# FPGA_System_Monitor.net
KiCad netlist of a schematic drawn in Altium Designer
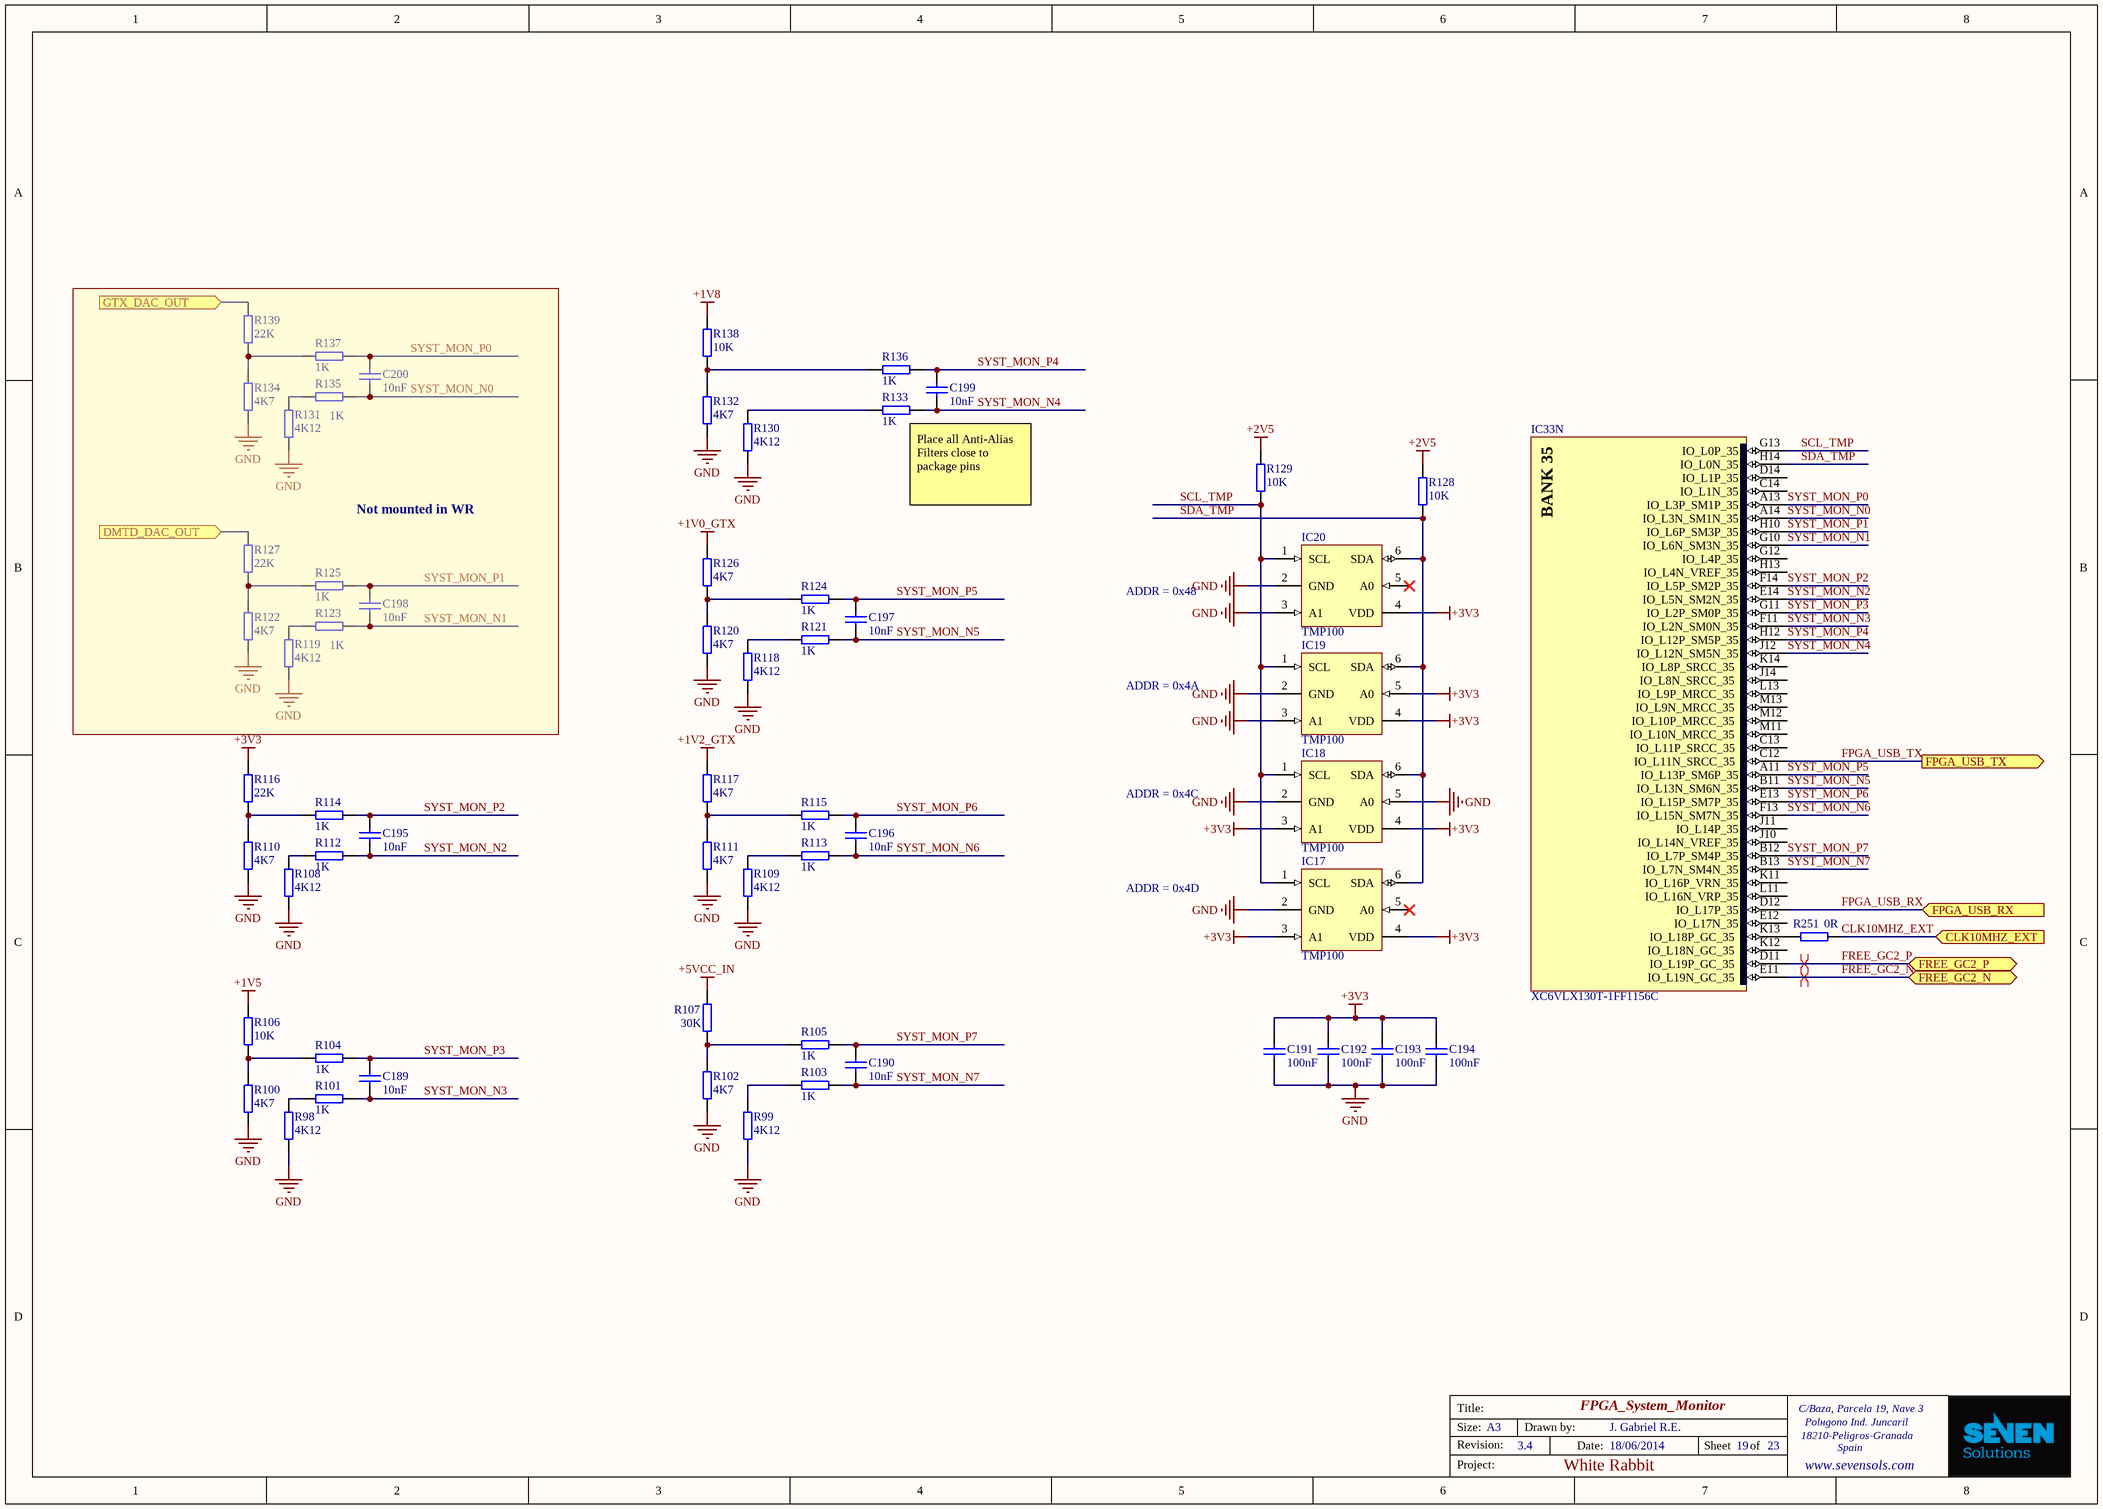
[diagram p0: FPGA_System_Monitor.SchDoc]

(export (version "E")
  (design (tool "Eeschema 10.0.6"))
  (components
    (comp (ref "C189")
      (value "10nF")
      (footprint "CC1005-0402")
      (description "Capacitor")
      (fields
        (field (name "TOLERANCE") "±10%")
        (field (name "VOLTAGE") "25V")
        (field (name "PUBLISHER") "Altium Limited")
      )
      (libsource (lib "wr_switch") (part "Cap"))
    )
    (comp (ref "C190")
      (value "10nF")
      (footprint "CC1005-0402")
      (description "Capacitor")
      (fields
        (field (name "TOLERANCE") "±10%")
        (field (name "VOLTAGE") "25V")
        (field (name "PUBLISHER") "Altium Limited")
      )
      (libsource (lib "wr_switch") (part "Cap"))
    )
    (comp (ref "C191")
      (value "100nF")
      (footprint "CC1005-0402")
      (description "Capacitor")
      (fields
        (field (name "TOLERANCE") "±10%")
        (field (name "VOLTAGE") "16V")
        (field (name "PUBLISHER") "Altium Limited")
      )
      (libsource (lib "wr_switch") (part "Cap"))
    )
    (comp (ref "C192")
      (value "100nF")
      (footprint "CC1005-0402")
      (description "Capacitor")
      (fields
        (field (name "TOLERANCE") "±10%")
        (field (name "VOLTAGE") "16V")
        (field (name "PUBLISHER") "Altium Limited")
      )
      (libsource (lib "wr_switch") (part "Cap"))
    )
    (comp (ref "C193")
      (value "100nF")
      (footprint "CC1005-0402")
      (description "Capacitor")
      (fields
        (field (name "TOLERANCE") "±10%")
        (field (name "VOLTAGE") "16V")
        (field (name "PUBLISHER") "Altium Limited")
      )
      (libsource (lib "wr_switch") (part "Cap"))
    )
    (comp (ref "C194")
      (value "100nF")
      (footprint "CC1005-0402")
      (description "Capacitor")
      (fields
        (field (name "TOLERANCE") "±10%")
        (field (name "VOLTAGE") "16V")
        (field (name "PUBLISHER") "Altium Limited")
      )
      (libsource (lib "wr_switch") (part "Cap"))
    )
    (comp (ref "C195")
      (value "10nF")
      (footprint "CC1005-0402")
      (description "Capacitor")
      (fields
        (field (name "TOLERANCE") "±10%")
        (field (name "VOLTAGE") "25V")
        (field (name "PUBLISHER") "Altium Limited")
      )
      (libsource (lib "wr_switch") (part "Cap"))
    )
    (comp (ref "C196")
      (value "10nF")
      (footprint "CC1005-0402")
      (description "Capacitor")
      (fields
        (field (name "TOLERANCE") "±10%")
        (field (name "VOLTAGE") "25V")
        (field (name "PUBLISHER") "Altium Limited")
      )
      (libsource (lib "wr_switch") (part "Cap"))
    )
    (comp (ref "C197")
      (value "10nF")
      (footprint "CC1005-0402")
      (description "Capacitor")
      (fields
        (field (name "TOLERANCE") "±10%")
        (field (name "VOLTAGE") "25V")
        (field (name "PUBLISHER") "Altium Limited")
      )
      (libsource (lib "wr_switch") (part "Cap"))
    )
    (comp (ref "C198")
      (value "10nF")
      (footprint "CC1005-0402")
      (description "Capacitor")
      (fields
        (field (name "TOLERANCE") "±10%")
        (field (name "VOLTAGE") "25V")
        (field (name "PUBLISHER") "Altium Limited")
      )
      (libsource (lib "wr_switch") (part "Cap"))
    )
    (comp (ref "C199")
      (value "10nF")
      (footprint "CC1005-0402")
      (description "Capacitor")
      (fields
        (field (name "TOLERANCE") "±10%")
        (field (name "VOLTAGE") "25V")
        (field (name "PUBLISHER") "Altium Limited")
      )
      (libsource (lib "wr_switch") (part "Cap"))
    )
    (comp (ref "C200")
      (value "10nF")
      (footprint "CC1005-0402")
      (description "Capacitor")
      (fields
        (field (name "TOLERANCE") "±10%")
        (field (name "VOLTAGE") "25V")
        (field (name "PUBLISHER") "Altium Limited")
      )
      (libsource (lib "wr_switch") (part "Cap"))
    )
    (comp (ref "IC17")
      (value "TMP100")
      (footprint "SOT23A-6L")
      (description "I2C temp. sensor")
      (libsource (lib "wr_switch") (part "TMP100"))
    )
    (comp (ref "IC18")
      (value "TMP100")
      (footprint "SOT23A-6L")
      (description "I2C temp. sensor")
      (libsource (lib "wr_switch") (part "TMP100"))
    )
    (comp (ref "IC19")
      (value "TMP100")
      (footprint "SOT23A-6L")
      (description "I2C temp. sensor")
      (libsource (lib "wr_switch") (part "TMP100"))
    )
    (comp (ref "IC20")
      (value "TMP100")
      (footprint "SOT23A-6L")
      (description "I2C temp. sensor")
      (libsource (lib "wr_switch") (part "TMP100"))
    )
    (comp (ref "IC33")
      (value "XC6VLX130T-1FF1156C")
      (footprint "FF1156")
      (fields (field (name "PUBLISHER") "Altium Limited"))
      (libsource (lib "Xilinx Virtex-6") (part "XC6VLX130T-1FF1156C"))
    )
    (comp (ref "R98")
      (value "4K12")
      (footprint "0402")
      (description "SMD Resistor")
      (fields (field (name "TOLERANCE") "±1%"))
      (libsource (lib "wr_switch") (part "RES_SMD"))
    )
    (comp (ref "R99")
      (value "4K12")
      (footprint "0402")
      (description "SMD Resistor")
      (fields (field (name "TOLERANCE") "±1%"))
      (libsource (lib "wr_switch") (part "RES_SMD"))
    )
    (comp (ref "R100")
      (value "4K7")
      (footprint "0402")
      (description "SMD Resistor")
      (fields (field (name "TOLERANCE") "±1%"))
      (libsource (lib "wr_switch") (part "RES_SMD"))
    )
    (comp (ref "R101")
      (value "1K")
      (footprint "0402")
      (description "SMD Resistor")
      (fields (field (name "TOLERANCE") "±1%"))
      (libsource (lib "wr_switch") (part "RES_SMD"))
    )
    (comp (ref "R102")
      (value "4K7")
      (footprint "0402")
      (description "SMD Resistor")
      (fields (field (name "TOLERANCE") "±1%"))
      (libsource (lib "wr_switch") (part "RES_SMD"))
    )
    (comp (ref "R103")
      (value "1K")
      (footprint "0402")
      (description "SMD Resistor")
      (fields (field (name "TOLERANCE") "±1%"))
      (libsource (lib "wr_switch") (part "RES_SMD"))
    )
    (comp (ref "R104")
      (value "1K")
      (footprint "0402")
      (description "SMD Resistor")
      (fields (field (name "TOLERANCE") "±1%"))
      (libsource (lib "wr_switch") (part "RES_SMD"))
    )
    (comp (ref "R105")
      (value "1K")
      (footprint "0402")
      (description "SMD Resistor")
      (fields (field (name "TOLERANCE") "±1%"))
      (libsource (lib "wr_switch") (part "RES_SMD"))
    )
    (comp (ref "R106")
      (value "10K")
      (footprint "0402")
      (description "SMD Resistor")
      (fields (field (name "TOLERANCE") "±1%") (field (name "Comment") "10k"))
      (libsource (lib "wr_switch") (part "RES_SMD"))
    )
    (comp (ref "R107")
      (value "30K")
      (footprint "0402")
      (description "SMD Resistor")
      (fields (field (name "TOLERANCE") "±1%"))
      (libsource (lib "wr_switch") (part "RES_SMD"))
    )
    (comp (ref "R108")
      (value "4K12")
      (footprint "0402")
      (description "SMD Resistor")
      (fields (field (name "TOLERANCE") "±1%"))
      (libsource (lib "wr_switch") (part "RES_SMD"))
    )
    (comp (ref "R109")
      (value "4K12")
      (footprint "0402")
      (description "SMD Resistor")
      (fields (field (name "TOLERANCE") "±1%"))
      (libsource (lib "wr_switch") (part "RES_SMD"))
    )
    (comp (ref "R110")
      (value "4K7")
      (footprint "0402")
      (description "SMD Resistor")
      (fields (field (name "TOLERANCE") "±1%"))
      (libsource (lib "wr_switch") (part "RES_SMD"))
    )
    (comp (ref "R111")
      (value "4K7")
      (footprint "0402")
      (description "SMD Resistor")
      (fields (field (name "TOLERANCE") "±1%"))
      (libsource (lib "wr_switch") (part "RES_SMD"))
    )
    (comp (ref "R112")
      (value "1K")
      (footprint "0402")
      (description "SMD Resistor")
      (fields (field (name "TOLERANCE") "±1%"))
      (libsource (lib "wr_switch") (part "RES_SMD"))
    )
    (comp (ref "R113")
      (value "1K")
      (footprint "0402")
      (description "SMD Resistor")
      (fields (field (name "TOLERANCE") "±1%"))
      (libsource (lib "wr_switch") (part "RES_SMD"))
    )
    (comp (ref "R114")
      (value "1K")
      (footprint "0402")
      (description "SMD Resistor")
      (fields (field (name "TOLERANCE") "±1%"))
      (libsource (lib "wr_switch") (part "RES_SMD"))
    )
    (comp (ref "R115")
      (value "1K")
      (footprint "0402")
      (description "SMD Resistor")
      (fields (field (name "TOLERANCE") "±1%"))
      (libsource (lib "wr_switch") (part "RES_SMD"))
    )
    (comp (ref "R116")
      (value "22K")
      (footprint "0402")
      (description "SMD Resistor")
      (fields (field (name "TOLERANCE") "±1%"))
      (libsource (lib "wr_switch") (part "RES_SMD"))
    )
    (comp (ref "R117")
      (value "4K7")
      (footprint "0402")
      (description "SMD Resistor")
      (fields (field (name "TOLERANCE") "±1%"))
      (libsource (lib "wr_switch") (part "RES_SMD"))
    )
    (comp (ref "R118")
      (value "4K12")
      (footprint "0402")
      (description "SMD Resistor")
      (fields (field (name "TOLERANCE") "±1%"))
      (libsource (lib "wr_switch") (part "RES_SMD"))
    )
    (comp (ref "R119")
      (value "4K12")
      (footprint "0402")
      (description "SMD Resistor")
      (fields (field (name "TOLERANCE") "±1%"))
      (libsource (lib "wr_switch") (part "RES_SMD"))
    )
    (comp (ref "R120")
      (value "4K7")
      (footprint "0402")
      (description "SMD Resistor")
      (fields (field (name "TOLERANCE") "±1%"))
      (libsource (lib "wr_switch") (part "RES_SMD"))
    )
    (comp (ref "R121")
      (value "1K")
      (footprint "0402")
      (description "SMD Resistor")
      (fields (field (name "TOLERANCE") "±1%"))
      (libsource (lib "wr_switch") (part "RES_SMD"))
    )
    (comp (ref "R122")
      (value "4K7")
      (footprint "0402")
      (description "SMD Resistor")
      (fields (field (name "TOLERANCE") "±1%"))
      (libsource (lib "wr_switch") (part "RES_SMD"))
    )
    (comp (ref "R123")
      (value "1K")
      (footprint "0402")
      (description "SMD Resistor")
      (fields (field (name "TOLERANCE") "±1%"))
      (libsource (lib "wr_switch") (part "RES_SMD"))
    )
    (comp (ref "R124")
      (value "1K")
      (footprint "0402")
      (description "SMD Resistor")
      (fields (field (name "TOLERANCE") "±1%"))
      (libsource (lib "wr_switch") (part "RES_SMD"))
    )
    (comp (ref "R125")
      (value "1K")
      (footprint "0402")
      (description "SMD Resistor")
      (fields (field (name "TOLERANCE") "±1%"))
      (libsource (lib "wr_switch") (part "RES_SMD"))
    )
    (comp (ref "R126")
      (value "4K7")
      (footprint "0402")
      (description "SMD Resistor")
      (fields (field (name "TOLERANCE") "±1%"))
      (libsource (lib "wr_switch") (part "RES_SMD"))
    )
    (comp (ref "R127")
      (value "22K")
      (footprint "0402")
      (description "SMD Resistor")
      (fields (field (name "TOLERANCE") "±1%"))
      (libsource (lib "wr_switch") (part "RES_SMD"))
    )
    (comp (ref "R128")
      (value "10K")
      (footprint "0402")
      (description "SMD Resistor")
      (fields (field (name "TOLERANCE") "±1%") (field (name "Comment") "10k"))
      (libsource (lib "wr_switch") (part "RES_SMD"))
    )
    (comp (ref "R129")
      (value "10K")
      (footprint "0402")
      (description "SMD Resistor")
      (fields (field (name "TOLERANCE") "±1%") (field (name "Comment") "10k"))
      (libsource (lib "wr_switch") (part "RES_SMD"))
    )
    (comp (ref "R130")
      (value "4K12")
      (footprint "0402")
      (description "SMD Resistor")
      (fields (field (name "TOLERANCE") "±1%"))
      (libsource (lib "wr_switch") (part "RES_SMD"))
    )
    (comp (ref "R131")
      (value "4K12")
      (footprint "0402")
      (description "SMD Resistor")
      (fields (field (name "TOLERANCE") "±1%"))
      (libsource (lib "wr_switch") (part "RES_SMD"))
    )
    (comp (ref "R132")
      (value "4K7")
      (footprint "0402")
      (description "SMD Resistor")
      (fields (field (name "TOLERANCE") "±1%"))
      (libsource (lib "wr_switch") (part "RES_SMD"))
    )
    (comp (ref "R133")
      (value "1K")
      (footprint "0402")
      (description "SMD Resistor")
      (fields (field (name "TOLERANCE") "±1%"))
      (libsource (lib "wr_switch") (part "RES_SMD"))
    )
    (comp (ref "R134")
      (value "4K7")
      (footprint "0402")
      (description "SMD Resistor")
      (fields (field (name "TOLERANCE") "±1%"))
      (libsource (lib "wr_switch") (part "RES_SMD"))
    )
    (comp (ref "R135")
      (value "1K")
      (footprint "0402")
      (description "SMD Resistor")
      (fields (field (name "TOLERANCE") "±1%"))
      (libsource (lib "wr_switch") (part "RES_SMD"))
    )
    (comp (ref "R136")
      (value "1K")
      (footprint "0402")
      (description "SMD Resistor")
      (fields (field (name "TOLERANCE") "±1%"))
      (libsource (lib "wr_switch") (part "RES_SMD"))
    )
    (comp (ref "R137")
      (value "1K")
      (footprint "0402")
      (description "SMD Resistor")
      (fields (field (name "TOLERANCE") "±1%"))
      (libsource (lib "wr_switch") (part "RES_SMD"))
    )
    (comp (ref "R138")
      (value "10K")
      (footprint "0402")
      (description "SMD Resistor")
      (fields (field (name "TOLERANCE") "±1%") (field (name "Comment") "10k"))
      (libsource (lib "wr_switch") (part "RES_SMD"))
    )
    (comp (ref "R139")
      (value "22K")
      (footprint "0402")
      (description "SMD Resistor")
      (fields (field (name "TOLERANCE") "±1%"))
      (libsource (lib "wr_switch") (part "RES_SMD"))
    )
    (comp (ref "R251")
      (value "0R")
      (footprint "0402")
      (description "SMD Resistor")
      (fields (field (name "TOLERANCE") "Jumper"))
      (libsource (lib "wr_switch") (part "RES_SMD"))
    )
  )
  (nets
    (net (code "1") (name "+1V0_GTX") (class "Default")
      (node (ref "R126") (pin "2") (pinfunction "2_2") (pintype "passive"))
    )
    (net (code "2") (name "+1V2_GTX") (class "Default")
      (node (ref "R117") (pin "2") (pinfunction "2_2") (pintype "passive"))
    )
    (net (code "3") (name "+1V5") (class "Default")
      (node (ref "R106") (pin "2") (pinfunction "2_2") (pintype "passive"))
    )
    (net (code "4") (name "+1V8") (class "Default")
      (node (ref "R138") (pin "2") (pinfunction "2_2") (pintype "passive"))
    )
    (net (code "5") (name "+2V5") (class "Default")
      (node (ref "R128") (pin "2") (pinfunction "2_2") (pintype "passive"))
      (node (ref "R129") (pin "2") (pinfunction "2_2") (pintype "passive"))
    )
    (net (code "6") (name "+3V3") (class "Default")
      (node (ref "C191") (pin "1") (pinfunction "1_1") (pintype "passive"))
      (node (ref "C192") (pin "1") (pinfunction "1_1") (pintype "passive"))
      (node (ref "C193") (pin "1") (pinfunction "1_1") (pintype "passive"))
      (node (ref "C194") (pin "1") (pinfunction "1_1") (pintype "passive"))
      (node (ref "IC17") (pin "3") (pinfunction "A1_3") (pintype "input"))
      (node (ref "IC17") (pin "4") (pinfunction "VDD_4") (pintype "power_in"))
      (node (ref "IC18") (pin "3") (pinfunction "A1_3") (pintype "input"))
      (node (ref "IC18") (pin "4") (pinfunction "VDD_4") (pintype "power_in"))
      (node (ref "IC19") (pin "4") (pinfunction "VDD_4") (pintype "power_in"))
      (node (ref "IC19") (pin "5") (pinfunction "A0_5") (pintype "input"))
      (node (ref "IC20") (pin "4") (pinfunction "VDD_4") (pintype "power_in"))
      (node (ref "R116") (pin "2") (pinfunction "2_2") (pintype "passive"))
    )
    (net (code "7") (name "+5VCC_IN") (class "Default")
      (node (ref "R107") (pin "2") (pinfunction "2_2") (pintype "passive"))
    )
    (net (code "8") (name "/CLK10MHZ_EXT") (class "Default")
      (node (ref "R251") (pin "1") (pinfunction "1_1") (pintype "passive"))
    )
    (net (code "9") (name "/DMTD_DAC_OUT") (class "Default")
      (node (ref "R127") (pin "2") (pinfunction "2_2") (pintype "passive"))
    )
    (net (code "10") (name "/FPGA_USB_RX") (class "Default")
      (node (ref "IC33") (pin "D12") (pinfunction "IO_L17P_35_D12") (pintype "bidirectional"))
    )
    (net (code "11") (name "/FPGA_USB_TX") (class "Default")
      (node (ref "IC33") (pin "C12") (pinfunction "IO_L11N_SRCC_35_C12") (pintype "bidirectional"))
    )
    (net (code "12") (name "/FREE_GC2_N") (class "Default")
      (node (ref "IC33") (pin "E11") (pinfunction "IO_L19N_GC_35_E11") (pintype "bidirectional"))
    )
    (net (code "13") (name "/FREE_GC2_P") (class "Default")
      (node (ref "IC33") (pin "D11") (pinfunction "IO_L19P_GC_35_D11") (pintype "bidirectional"))
    )
    (net (code "14") (name "/GTX_DAC_OUT") (class "Default")
      (node (ref "R139") (pin "2") (pinfunction "2_2") (pintype "passive"))
    )
    (net (code "15") (name "/SCL_TMP") (class "Default")
      (node (ref "IC17") (pin "1") (pinfunction "SCL_1") (pintype "input"))
      (node (ref "IC18") (pin "1") (pinfunction "SCL_1") (pintype "input"))
      (node (ref "IC19") (pin "1") (pinfunction "SCL_1") (pintype "input"))
      (node (ref "IC20") (pin "1") (pinfunction "SCL_1") (pintype "input"))
      (node (ref "IC33") (pin "G13") (pinfunction "IO_L0P_35_G13") (pintype "bidirectional"))
      (node (ref "R129") (pin "1") (pinfunction "1_1") (pintype "passive"))
    )
    (net (code "16") (name "/SDA_TMP") (class "Default")
      (node (ref "IC17") (pin "6") (pinfunction "SDA_6") (pintype "bidirectional"))
      (node (ref "IC18") (pin "6") (pinfunction "SDA_6") (pintype "bidirectional"))
      (node (ref "IC19") (pin "6") (pinfunction "SDA_6") (pintype "bidirectional"))
      (node (ref "IC20") (pin "6") (pinfunction "SDA_6") (pintype "bidirectional"))
      (node (ref "IC33") (pin "H14") (pinfunction "IO_L0N_35_H14") (pintype "bidirectional"))
      (node (ref "R128") (pin "1") (pinfunction "1_1") (pintype "passive"))
    )
    (net (code "17") (name "/SYST_MON_N0") (class "Default")
      (node (ref "C200") (pin "1") (pinfunction "1_1") (pintype "passive"))
      (node (ref "IC33") (pin "A14") (pinfunction "IO_L3N_SM1N_35_A14") (pintype "bidirectional"))
      (node (ref "R135") (pin "1") (pinfunction "1_1") (pintype "passive"))
    )
    (net (code "18") (name "/SYST_MON_N1") (class "Default")
      (node (ref "C198") (pin "1") (pinfunction "1_1") (pintype "passive"))
      (node (ref "IC33") (pin "G10") (pinfunction "IO_L6N_SM3N_35_G10") (pintype "bidirectional"))
      (node (ref "R123") (pin "1") (pinfunction "1_1") (pintype "passive"))
    )
    (net (code "19") (name "/SYST_MON_N2") (class "Default")
      (node (ref "C195") (pin "1") (pinfunction "1_1") (pintype "passive"))
      (node (ref "IC33") (pin "E14") (pinfunction "IO_L5N_SM2N_35_E14") (pintype "bidirectional"))
      (node (ref "R112") (pin "1") (pinfunction "1_1") (pintype "passive"))
    )
    (net (code "20") (name "/SYST_MON_N3") (class "Default")
      (node (ref "C189") (pin "1") (pinfunction "1_1") (pintype "passive"))
      (node (ref "IC33") (pin "F11") (pinfunction "IO_L2N_SM0N_35_F11") (pintype "bidirectional"))
      (node (ref "R101") (pin "1") (pinfunction "1_1") (pintype "passive"))
    )
    (net (code "21") (name "/SYST_MON_N4") (class "Default")
      (node (ref "C199") (pin "1") (pinfunction "1_1") (pintype "passive"))
      (node (ref "IC33") (pin "J12") (pinfunction "IO_L12N_SM5N_35_J12") (pintype "bidirectional"))
      (node (ref "R133") (pin "1") (pinfunction "1_1") (pintype "passive"))
    )
    (net (code "22") (name "/SYST_MON_N5") (class "Default")
      (node (ref "C197") (pin "1") (pinfunction "1_1") (pintype "passive"))
      (node (ref "IC33") (pin "B11") (pinfunction "IO_L13N_SM6N_35_B11") (pintype "bidirectional"))
      (node (ref "R121") (pin "1") (pinfunction "1_1") (pintype "passive"))
    )
    (net (code "23") (name "/SYST_MON_N6") (class "Default")
      (node (ref "C196") (pin "1") (pinfunction "1_1") (pintype "passive"))
      (node (ref "IC33") (pin "F13") (pinfunction "IO_L15N_SM7N_35_F13") (pintype "bidirectional"))
      (node (ref "R113") (pin "1") (pinfunction "1_1") (pintype "passive"))
    )
    (net (code "24") (name "/SYST_MON_N7") (class "Default")
      (node (ref "C190") (pin "1") (pinfunction "1_1") (pintype "passive"))
      (node (ref "IC33") (pin "B13") (pinfunction "IO_L7N_SM4N_35_B13") (pintype "bidirectional"))
      (node (ref "R103") (pin "1") (pinfunction "1_1") (pintype "passive"))
    )
    (net (code "25") (name "/SYST_MON_P0") (class "Default")
      (node (ref "C200") (pin "2") (pinfunction "2_2") (pintype "passive"))
      (node (ref "IC33") (pin "A13") (pinfunction "IO_L3P_SM1P_35_A13") (pintype "bidirectional"))
      (node (ref "R137") (pin "1") (pinfunction "1_1") (pintype "passive"))
    )
    (net (code "26") (name "/SYST_MON_P1") (class "Default")
      (node (ref "C198") (pin "2") (pinfunction "2_2") (pintype "passive"))
      (node (ref "IC33") (pin "H10") (pinfunction "IO_L6P_SM3P_35_H10") (pintype "bidirectional"))
      (node (ref "R125") (pin "1") (pinfunction "1_1") (pintype "passive"))
    )
    (net (code "27") (name "/SYST_MON_P2") (class "Default")
      (node (ref "C195") (pin "2") (pinfunction "2_2") (pintype "passive"))
      (node (ref "IC33") (pin "F14") (pinfunction "IO_L5P_SM2P_35_F14") (pintype "bidirectional"))
      (node (ref "R114") (pin "1") (pinfunction "1_1") (pintype "passive"))
    )
    (net (code "28") (name "/SYST_MON_P3") (class "Default")
      (node (ref "C189") (pin "2") (pinfunction "2_2") (pintype "passive"))
      (node (ref "IC33") (pin "G11") (pinfunction "IO_L2P_SM0P_35_G11") (pintype "bidirectional"))
      (node (ref "R104") (pin "1") (pinfunction "1_1") (pintype "passive"))
    )
    (net (code "29") (name "/SYST_MON_P4") (class "Default")
      (node (ref "C199") (pin "2") (pinfunction "2_2") (pintype "passive"))
      (node (ref "IC33") (pin "H12") (pinfunction "IO_L12P_SM5P_35_H12") (pintype "bidirectional"))
      (node (ref "R136") (pin "1") (pinfunction "1_1") (pintype "passive"))
    )
    (net (code "30") (name "/SYST_MON_P5") (class "Default")
      (node (ref "C197") (pin "2") (pinfunction "2_2") (pintype "passive"))
      (node (ref "IC33") (pin "A11") (pinfunction "IO_L13P_SM6P_35_A11") (pintype "bidirectional"))
      (node (ref "R124") (pin "1") (pinfunction "1_1") (pintype "passive"))
    )
    (net (code "31") (name "/SYST_MON_P6") (class "Default")
      (node (ref "C196") (pin "2") (pinfunction "2_2") (pintype "passive"))
      (node (ref "IC33") (pin "E13") (pinfunction "IO_L15P_SM7P_35_E13") (pintype "bidirectional"))
      (node (ref "R115") (pin "1") (pinfunction "1_1") (pintype "passive"))
    )
    (net (code "32") (name "/SYST_MON_P7") (class "Default")
      (node (ref "C190") (pin "2") (pinfunction "2_2") (pintype "passive"))
      (node (ref "IC33") (pin "B12") (pinfunction "IO_L7P_SM4P_35_B12") (pintype "bidirectional"))
      (node (ref "R105") (pin "1") (pinfunction "1_1") (pintype "passive"))
    )
    (net (code "33") (name "GND") (class "Default")
      (node (ref "C191") (pin "2") (pinfunction "2_2") (pintype "passive"))
      (node (ref "C192") (pin "2") (pinfunction "2_2") (pintype "passive"))
      (node (ref "C193") (pin "2") (pinfunction "2_2") (pintype "passive"))
      (node (ref "C194") (pin "2") (pinfunction "2_2") (pintype "passive"))
      (node (ref "IC17") (pin "2") (pinfunction "GND_2") (pintype "power_in"))
      (node (ref "IC18") (pin "2") (pinfunction "GND_2") (pintype "power_in"))
      (node (ref "IC18") (pin "5") (pinfunction "A0_5") (pintype "input"))
      (node (ref "IC19") (pin "2") (pinfunction "GND_2") (pintype "power_in"))
      (node (ref "IC19") (pin "3") (pinfunction "A1_3") (pintype "input"))
      (node (ref "IC20") (pin "2") (pinfunction "GND_2") (pintype "power_in"))
      (node (ref "IC20") (pin "3") (pinfunction "A1_3") (pintype "input"))
      (node (ref "R100") (pin "1") (pinfunction "1_1") (pintype "passive"))
      (node (ref "R102") (pin "1") (pinfunction "1_1") (pintype "passive"))
      (node (ref "R108") (pin "1") (pinfunction "1_1") (pintype "passive"))
      (node (ref "R109") (pin "1") (pinfunction "1_1") (pintype "passive"))
      (node (ref "R110") (pin "1") (pinfunction "1_1") (pintype "passive"))
      (node (ref "R111") (pin "1") (pinfunction "1_1") (pintype "passive"))
      (node (ref "R118") (pin "1") (pinfunction "1_1") (pintype "passive"))
      (node (ref "R119") (pin "1") (pinfunction "1_1") (pintype "passive"))
      (node (ref "R120") (pin "1") (pinfunction "1_1") (pintype "passive"))
      (node (ref "R122") (pin "1") (pinfunction "1_1") (pintype "passive"))
      (node (ref "R130") (pin "1") (pinfunction "1_1") (pintype "passive"))
      (node (ref "R131") (pin "1") (pinfunction "1_1") (pintype "passive"))
      (node (ref "R132") (pin "1") (pinfunction "1_1") (pintype "passive"))
      (node (ref "R134") (pin "1") (pinfunction "1_1") (pintype "passive"))
      (node (ref "R98") (pin "1") (pinfunction "1_1") (pintype "passive"))
      (node (ref "R99") (pin "1") (pinfunction "1_1") (pintype "passive"))
    )
    (net (code "34") (name "Net-(IC33N-IO_L18P_GC_35)") (class "Default")
      (node (ref "IC33") (pin "K13") (pinfunction "IO_L18P_GC_35_K13") (pintype "bidirectional"))
      (node (ref "R251") (pin "2") (pinfunction "2_2") (pintype "passive"))
    )
    (net (code "35") (name "Net-(R100-Pad2)") (class "Default")
      (node (ref "R100") (pin "2") (pinfunction "2_2") (pintype "passive"))
      (node (ref "R104") (pin "2") (pinfunction "2_2") (pintype "passive"))
      (node (ref "R106") (pin "1") (pinfunction "1_1") (pintype "passive"))
    )
    (net (code "36") (name "Net-(R101-Pad2)") (class "Default")
      (node (ref "R101") (pin "2") (pinfunction "2_2") (pintype "passive"))
      (node (ref "R98") (pin "2") (pinfunction "2_2") (pintype "passive"))
    )
    (net (code "37") (name "Net-(R102-Pad2)") (class "Default")
      (node (ref "R102") (pin "2") (pinfunction "2_2") (pintype "passive"))
      (node (ref "R105") (pin "2") (pinfunction "2_2") (pintype "passive"))
      (node (ref "R107") (pin "1") (pinfunction "1_1") (pintype "passive"))
    )
    (net (code "38") (name "Net-(R103-Pad2)") (class "Default")
      (node (ref "R103") (pin "2") (pinfunction "2_2") (pintype "passive"))
      (node (ref "R99") (pin "2") (pinfunction "2_2") (pintype "passive"))
    )
    (net (code "39") (name "Net-(R108-Pad2)") (class "Default")
      (node (ref "R108") (pin "2") (pinfunction "2_2") (pintype "passive"))
      (node (ref "R112") (pin "2") (pinfunction "2_2") (pintype "passive"))
    )
    (net (code "40") (name "Net-(R109-Pad2)") (class "Default")
      (node (ref "R109") (pin "2") (pinfunction "2_2") (pintype "passive"))
      (node (ref "R113") (pin "2") (pinfunction "2_2") (pintype "passive"))
    )
    (net (code "41") (name "Net-(R110-Pad2)") (class "Default")
      (node (ref "R110") (pin "2") (pinfunction "2_2") (pintype "passive"))
      (node (ref "R114") (pin "2") (pinfunction "2_2") (pintype "passive"))
      (node (ref "R116") (pin "1") (pinfunction "1_1") (pintype "passive"))
    )
    (net (code "42") (name "Net-(R111-Pad2)") (class "Default")
      (node (ref "R111") (pin "2") (pinfunction "2_2") (pintype "passive"))
      (node (ref "R115") (pin "2") (pinfunction "2_2") (pintype "passive"))
      (node (ref "R117") (pin "1") (pinfunction "1_1") (pintype "passive"))
    )
    (net (code "43") (name "Net-(R118-Pad2)") (class "Default")
      (node (ref "R118") (pin "2") (pinfunction "2_2") (pintype "passive"))
      (node (ref "R121") (pin "2") (pinfunction "2_2") (pintype "passive"))
    )
    (net (code "44") (name "Net-(R119-Pad2)") (class "Default")
      (node (ref "R119") (pin "2") (pinfunction "2_2") (pintype "passive"))
      (node (ref "R123") (pin "2") (pinfunction "2_2") (pintype "passive"))
    )
    (net (code "45") (name "Net-(R120-Pad2)") (class "Default")
      (node (ref "R120") (pin "2") (pinfunction "2_2") (pintype "passive"))
      (node (ref "R124") (pin "2") (pinfunction "2_2") (pintype "passive"))
      (node (ref "R126") (pin "1") (pinfunction "1_1") (pintype "passive"))
    )
    (net (code "46") (name "Net-(R122-Pad2)") (class "Default")
      (node (ref "R122") (pin "2") (pinfunction "2_2") (pintype "passive"))
      (node (ref "R125") (pin "2") (pinfunction "2_2") (pintype "passive"))
      (node (ref "R127") (pin "1") (pinfunction "1_1") (pintype "passive"))
    )
    (net (code "47") (name "Net-(R130-Pad2)") (class "Default")
      (node (ref "R130") (pin "2") (pinfunction "2_2") (pintype "passive"))
      (node (ref "R133") (pin "2") (pinfunction "2_2") (pintype "passive"))
    )
    (net (code "48") (name "Net-(R131-Pad2)") (class "Default")
      (node (ref "R131") (pin "2") (pinfunction "2_2") (pintype "passive"))
      (node (ref "R135") (pin "2") (pinfunction "2_2") (pintype "passive"))
    )
    (net (code "49") (name "Net-(R132-Pad2)") (class "Default")
      (node (ref "R132") (pin "2") (pinfunction "2_2") (pintype "passive"))
      (node (ref "R136") (pin "2") (pinfunction "2_2") (pintype "passive"))
      (node (ref "R138") (pin "1") (pinfunction "1_1") (pintype "passive"))
    )
    (net (code "50") (name "Net-(R134-Pad2)") (class "Default")
      (node (ref "R134") (pin "2") (pinfunction "2_2") (pintype "passive"))
      (node (ref "R137") (pin "2") (pinfunction "2_2") (pintype "passive"))
      (node (ref "R139") (pin "1") (pinfunction "1_1") (pintype "passive"))
    )
    (net (code "51") (name "unconnected-(IC17-A0-Pad5)") (class "Default")
      (node (ref "IC17") (pin "5") (pinfunction "A0_5") (pintype "input+no_connect"))
    )
    (net (code "52") (name "unconnected-(IC20-A0-Pad5)") (class "Default")
      (node (ref "IC20") (pin "5") (pinfunction "A0_5") (pintype "input+no_connect"))
    )
    (net (code "53") (name "unconnected-(IC33N-IO_L1N_35-PadC14)") (class "Default")
      (node (ref "IC33") (pin "C14") (pinfunction "IO_L1N_35_C14") (pintype "bidirectional"))
    )
    (net (code "54") (name "unconnected-(IC33N-IO_L1P_35-PadD14)") (class "Default")
      (node (ref "IC33") (pin "D14") (pinfunction "IO_L1P_35_D14") (pintype "bidirectional"))
    )
    (net (code "55") (name "unconnected-(IC33N-IO_L4N_VREF_35-PadH13)") (class "Default")
      (node (ref "IC33") (pin "H13") (pinfunction "IO_L4N_VREF_35_H13") (pintype "bidirectional"))
    )
    (net (code "56") (name "unconnected-(IC33N-IO_L4P_35-PadG12)") (class "Default")
      (node (ref "IC33") (pin "G12") (pinfunction "IO_L4P_35_G12") (pintype "bidirectional"))
    )
    (net (code "57") (name "unconnected-(IC33N-IO_L8N_SRCC_35-PadJ14)") (class "Default")
      (node (ref "IC33") (pin "J14") (pinfunction "IO_L8N_SRCC_35_J14") (pintype "bidirectional"))
    )
    (net (code "58") (name "unconnected-(IC33N-IO_L8P_SRCC_35-PadK14)") (class "Default")
      (node (ref "IC33") (pin "K14") (pinfunction "IO_L8P_SRCC_35_K14") (pintype "bidirectional"))
    )
    (net (code "59") (name "unconnected-(IC33N-IO_L9N_MRCC_35-PadM13)") (class "Default")
      (node (ref "IC33") (pin "M13") (pinfunction "IO_L9N_MRCC_35_M13") (pintype "bidirectional"))
    )
    (net (code "60") (name "unconnected-(IC33N-IO_L9P_MRCC_35-PadL13)") (class "Default")
      (node (ref "IC33") (pin "L13") (pinfunction "IO_L9P_MRCC_35_L13") (pintype "bidirectional"))
    )
    (net (code "61") (name "unconnected-(IC33N-IO_L10N_MRCC_35-PadM11)") (class "Default")
      (node (ref "IC33") (pin "M11") (pinfunction "IO_L10N_MRCC_35_M11") (pintype "bidirectional"))
    )
    (net (code "62") (name "unconnected-(IC33N-IO_L10P_MRCC_35-PadM12)") (class "Default")
      (node (ref "IC33") (pin "M12") (pinfunction "IO_L10P_MRCC_35_M12") (pintype "bidirectional"))
    )
    (net (code "63") (name "unconnected-(IC33N-IO_L11P_SRCC_35-PadC13)") (class "Default")
      (node (ref "IC33") (pin "C13") (pinfunction "IO_L11P_SRCC_35_C13") (pintype "bidirectional"))
    )
    (net (code "64") (name "unconnected-(IC33N-IO_L14N_VREF_35-PadJ10)") (class "Default")
      (node (ref "IC33") (pin "J10") (pinfunction "IO_L14N_VREF_35_J10") (pintype "bidirectional"))
    )
    (net (code "65") (name "unconnected-(IC33N-IO_L14P_35-PadJ11)") (class "Default")
      (node (ref "IC33") (pin "J11") (pinfunction "IO_L14P_35_J11") (pintype "bidirectional"))
    )
    (net (code "66") (name "unconnected-(IC33N-IO_L16N_VRP_35-PadL11)") (class "Default")
      (node (ref "IC33") (pin "L11") (pinfunction "IO_L16N_VRP_35_L11") (pintype "bidirectional"))
    )
    (net (code "67") (name "unconnected-(IC33N-IO_L16P_VRN_35-PadK11)") (class "Default")
      (node (ref "IC33") (pin "K11") (pinfunction "IO_L16P_VRN_35_K11") (pintype "bidirectional"))
    )
    (net (code "68") (name "unconnected-(IC33N-IO_L17N_35-PadE12)") (class "Default")
      (node (ref "IC33") (pin "E12") (pinfunction "IO_L17N_35_E12") (pintype "bidirectional"))
    )
    (net (code "69") (name "unconnected-(IC33N-IO_L18N_GC_35-PadK12)") (class "Default")
      (node (ref "IC33") (pin "K12") (pinfunction "IO_L18N_GC_35_K12") (pintype "bidirectional"))
    )
  )
)
